# Antenna.net
KiCad netlist of a schematic drawn in Altium Designer
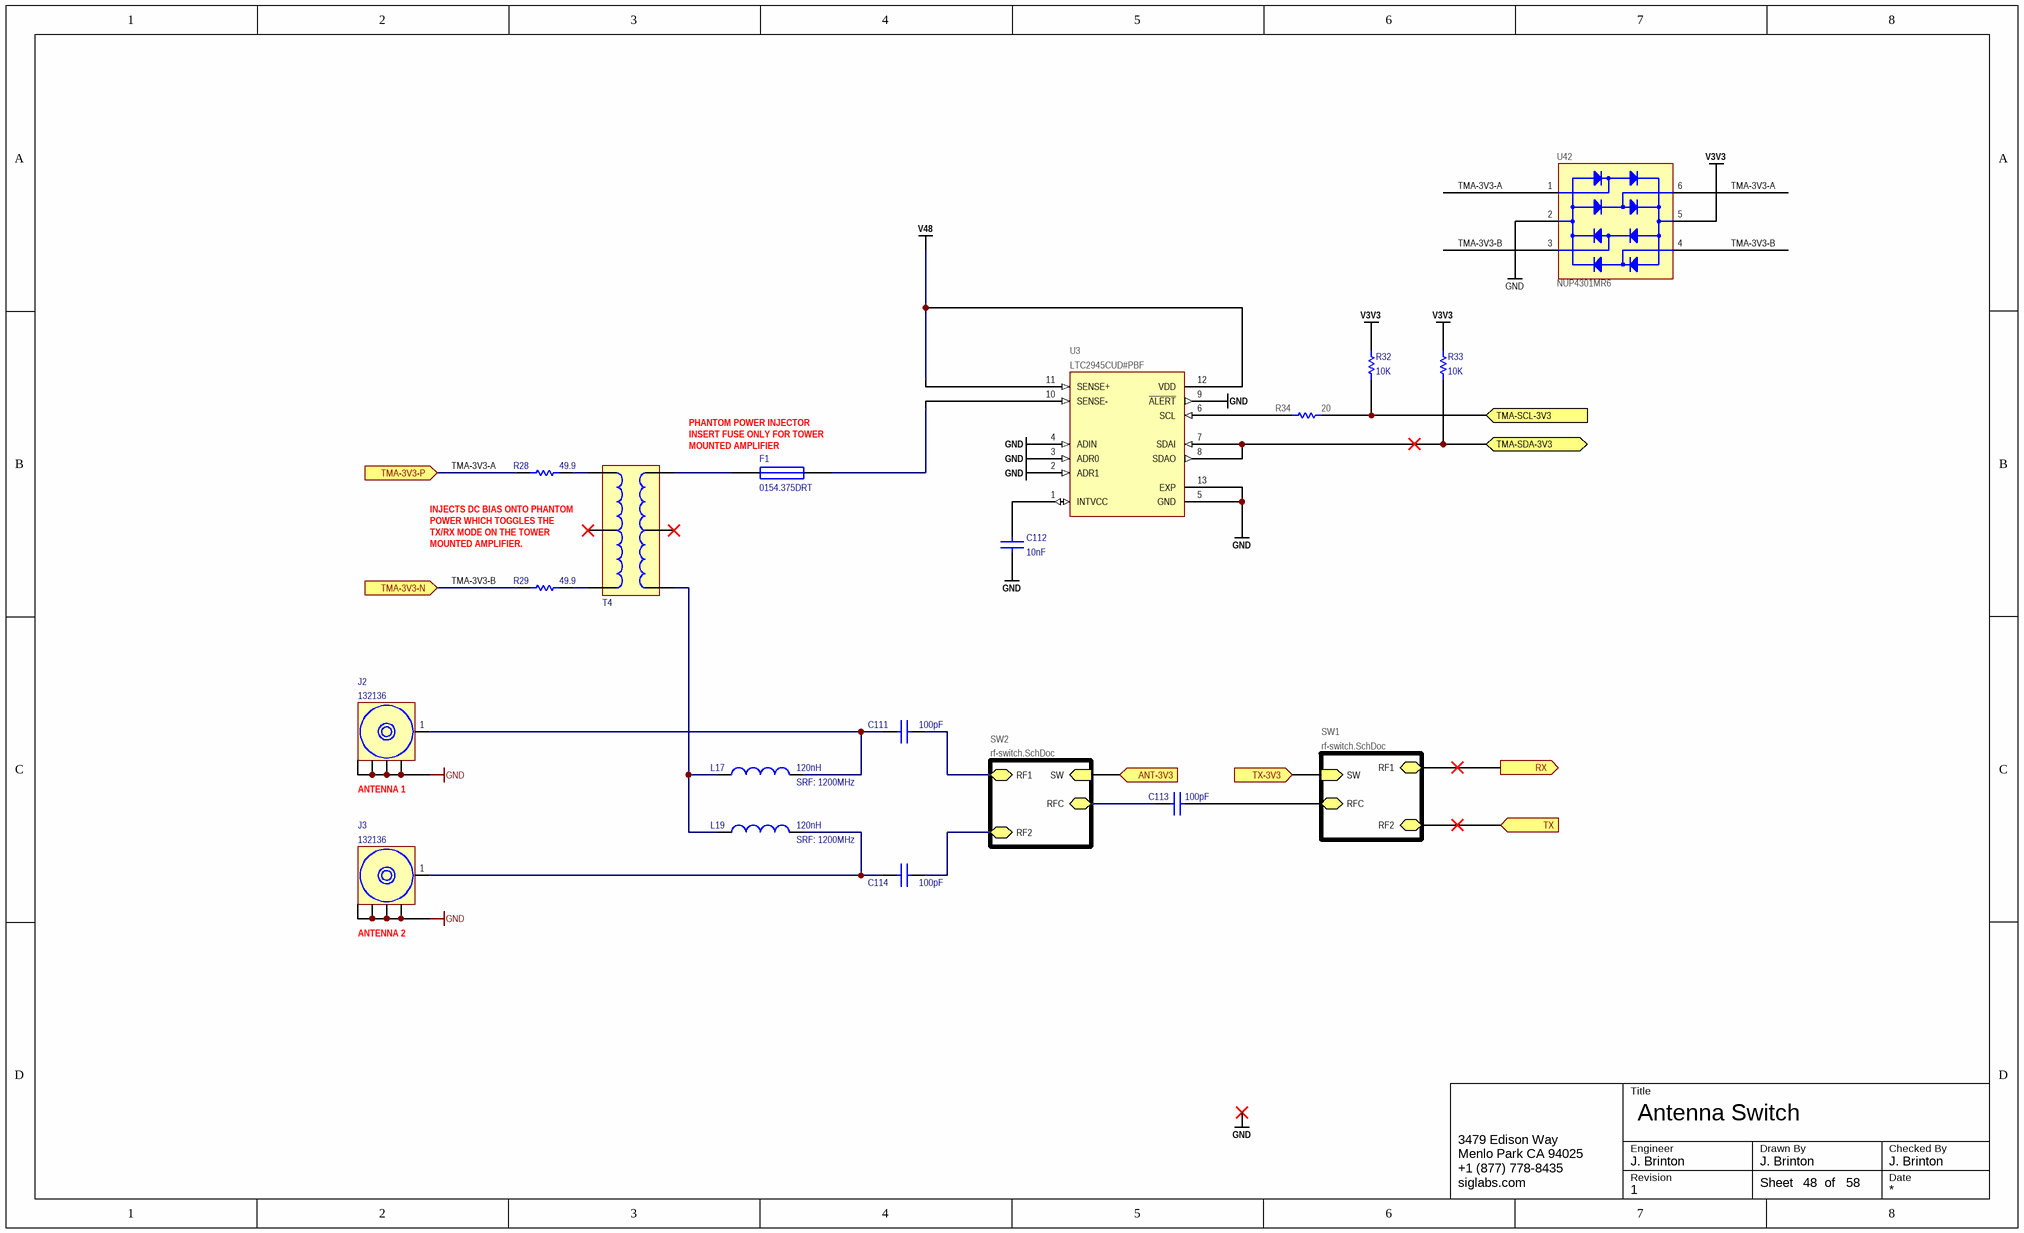
[diagram p0: Antenna.SchDoc]

(export (version "E")
  (design (tool "Eeschema 10.0.6"))
  (components
    (comp (ref "C111")
      (value "100pF")
      (footprint "CAPC100X50X55L25N")
      (description "Ceramic Capacitor 100pF ±5% 100V NP0 0402")
      (fields (field (name "VOLTAGE") "100V") (field (name "MANUFACTURER") "Kemet"))
      (libsource (lib "Graviton") (part "CAP 0603"))
    )
    (comp (ref "C112")
      (value "10nF")
      (footprint "CAPC100X50X55L25N")
      (description "Ceramic Capacitor 10nF ±10% 50V X7R 0402")
      (fields (field (name "VOLTAGE") "50V") (field (name "MANUFACTURER") "Murata"))
      (libsource (lib "Graviton") (part "CAP 0402"))
    )
    (comp (ref "C113")
      (value "100pF")
      (footprint "CAPC100X50X55L25N")
      (description "Ceramic Capacitor 100pF ±1% 25V NP0 0402")
      (fields (field (name "VOLTAGE") "25V") (field (name "MANUFACTURER") "Kemet"))
      (libsource (lib "Graviton") (part "CAP 0603"))
    )
    (comp (ref "C114")
      (value "100pF")
      (footprint "CAPC100X50X55L25N")
      (description "Ceramic Capacitor 100pF ±5% 100V NP0 0402")
      (fields (field (name "VOLTAGE") "100V") (field (name "MANUFACTURER") "Kemet"))
      (libsource (lib "Graviton") (part "CAP 0603"))
    )
    (comp (ref "F1")
      (value "0154.375DRT")
      (footprint "littelfuse:154")
      (description "154 OMNI-BLOK 0.375A Fuse and Holder")
      (fields (field (name "MANUFACTURER") "Littelfuse"))
      (libsource (lib "Miscellaneous Devices") (part "Fuse 1"))
    )
    (comp (ref "J2")
      (value "132136")
      (footprint "132136")
      (description "SMA Right Angle Connector COAX Female")
      (fields (field (name "MANUFACTURER") "Amphenol"))
      (libsource (lib "amphenol") (part "132136"))
    )
    (comp (ref "J3")
      (value "132136")
      (footprint "132136")
      (description "SMA Right Angle Connector COAX Female")
      (fields (field (name "MANUFACTURER") "Amphenol"))
      (libsource (lib "amphenol") (part "132136"))
    )
    (comp (ref "L17")
      (value "120nH")
      (footprint "0603")
      (description "Wirewound Inductor 120nH 1.1A 0603")
      (fields
        (field (name "MANUFACTURER") "Murata")
        (field (name "SRF") "1200MHz")
        (field (name "Comment") "LQW18CNR12J00D")
      )
      (libsource (lib "Graviton") (part "IND 0603"))
    )
    (comp (ref "L19")
      (value "120nH")
      (footprint "0603")
      (description "Wirewound Inductor 120nH 1.1A 0603")
      (fields
        (field (name "MANUFACTURER") "Murata")
        (field (name "SRF") "1200MHz")
        (field (name "Comment") "LQW18CNR12J00D")
      )
      (libsource (lib "Graviton") (part "IND 0603"))
    )
    (comp (ref "R28")
      (value "49.9")
      (footprint "generic:0603")
      (description "Thick Film Resistor 49.9 ±1% 0603")
      (fields (field (name "MANUFACTURER") "Panasonic") (field (name "TOLERANCE") "±1%"))
      (libsource (lib "generic") (part "RES 0603"))
    )
    (comp (ref "R29")
      (value "49.9")
      (footprint "generic:0603")
      (description "Thick Film Resistor 49.9 ±1% 0603")
      (fields (field (name "MANUFACTURER") "Panasonic") (field (name "TOLERANCE") "±1%"))
      (libsource (lib "generic") (part "RES 0603"))
    )
    (comp (ref "R32")
      (value "10K")
      (footprint "RESC1005X40N")
      (description "Thick Film 10k ±1% 0402")
      (fields (field (name "MANUFACTURER") "Panasonic") (field (name "TOLERANCE") "±1%"))
      (libsource (lib "Graviton") (part "RES 0402"))
    )
    (comp (ref "R33")
      (value "10K")
      (footprint "RESC1005X40N")
      (description "Thick Film 10k ±1% 0402")
      (fields (field (name "MANUFACTURER") "Panasonic") (field (name "TOLERANCE") "±1%"))
      (libsource (lib "Graviton") (part "RES 0402"))
    )
    (comp (ref "R34")
      (value "20")
      (footprint "RESC1005X40N")
      (description "Thick Film Resistor 20 ±1% 0.1W 75V 0402")
      (fields (field (name "TOLERANCE") "±1%") (field (name "MANUFACTURER") "Panasonic"))
      (libsource (lib "generic") (part "RES"))
    )
    (comp (ref "T4")
      (value "78253/35JC-R")
      (footprint "murata:78253/35JC-R")
      (description "Transformer")
      (fields (field (name "MANUFACTURER") "MuRata"))
      (libsource (lib "murata") (part "78253/35JC-R"))
    )
    (comp (ref "U3")
      (value "LTC2945CUD#PBF")
      (footprint "linear:QFN50P300X300X80-13N")
      (description "MS-System Monitor/Other Wide Range I2C Power Monitor %28SDAO%29")
      (fields (field (name "MF") "Linear Technology"))
      (libsource (lib "linear") (part "LTC2945CUD#PBF"))
    )
    (comp (ref "U42")
      (value "NUP4301MR6")
      (footprint "generic:SOT23-6")
      (description "4-Lane TVS Diode Array")
      (fields (field (name "MANUFACTURER") "On Semiconductor"))
      (libsource (lib "on_semi") (part "NUP4301MR6"))
    )
  )
  (nets
    (net (code "2") (name "/RF1") (class "Default")
      (node (ref "C111") (pin "1") (pinfunction "1_1") (pintype "passive"))
    )
    (net (code "3") (name "/RF2") (class "Default")
      (node (ref "C114") (pin "1") (pinfunction "1_1") (pintype "passive"))
    )
    (net (code "4") (name "/RFC") (class "Default")
      (node (ref "C113") (pin "1") (pinfunction "1_1") (pintype "passive"))
    )
    (net (code "5") (name "/RFC_1") (class "Default")
      (node (ref "C113") (pin "2") (pinfunction "2_2") (pintype "passive"))
    )
    (net (code "7") (name "/TMA-3V3-A") (class "Default")
      (node (ref "R28") (pin "1") (pinfunction "1_1") (pintype "passive"))
      (node (ref "U42") (pin "1") (pinfunction "A_1") (pintype "passive"))
      (node (ref "U42") (pin "6") (pinfunction "D_6") (pintype "passive"))
    )
    (net (code "8") (name "/TMA-3V3-B") (class "Default")
      (node (ref "R29") (pin "1") (pinfunction "1_1") (pintype "passive"))
      (node (ref "U42") (pin "3") (pinfunction "B_3") (pintype "passive"))
      (node (ref "U42") (pin "4") (pinfunction "C_4") (pintype "passive"))
    )
    (net (code "9") (name "/TMA-SCL-3V3") (class "Default")
      (node (ref "R32") (pin "1") (pinfunction "1_1") (pintype "passive"))
      (node (ref "R34") (pin "2") (pinfunction "2_2") (pintype "passive"))
    )
    (net (code "10") (name "/TMA-SDA-3V3") (class "Default")
      (node (ref "R33") (pin "1") (pinfunction "1_1") (pintype "passive"))
      (node (ref "U3") (pin "7") (pinfunction "SDAI_7") (pintype "input"))
      (node (ref "U3") (pin "8") (pinfunction "SDAO_8") (pintype "output"))
    )
    (net (code "13") (name "GND") (class "Default")
      (node (ref "C112") (pin "1") (pinfunction "1_1") (pintype "passive"))
      (node (ref "J2") (pin "2") (pinfunction "GND_2") (pintype "passive"))
      (node (ref "J2") (pin "3") (pinfunction "GND_3") (pintype "passive"))
      (node (ref "J2") (pin "4") (pinfunction "GND_4") (pintype "passive"))
      (node (ref "J2") (pin "5") (pinfunction "GND_5") (pintype "passive"))
      (node (ref "J3") (pin "2") (pinfunction "GND_2") (pintype "passive"))
      (node (ref "J3") (pin "3") (pinfunction "GND_3") (pintype "passive"))
      (node (ref "J3") (pin "4") (pinfunction "GND_4") (pintype "passive"))
      (node (ref "J3") (pin "5") (pinfunction "GND_5") (pintype "passive"))
      (node (ref "U3") (pin "13") (pinfunction "EXP_13") (pintype "power_in"))
      (node (ref "U3") (pin "2") (pinfunction "ADR1_2") (pintype "input"))
      (node (ref "U3") (pin "3") (pinfunction "ADR0_3") (pintype "input"))
      (node (ref "U3") (pin "4") (pinfunction "ADIN_4") (pintype "input"))
      (node (ref "U3") (pin "5") (pinfunction "GND_5") (pintype "power_in"))
      (node (ref "U3") (pin "9") (pinfunction "~{ALERT}_9") (pintype "output"))
      (node (ref "U42") (pin "2") (pinfunction "VN_2") (pintype "passive"))
    )
    (net (code "14") (name "Net-(F1-Pad1)") (class "Default")
      (node (ref "F1") (pin "1") (pinfunction "1_1") (pintype "passive"))
      (node (ref "T4") (pin "6") (pinfunction "6_6") (pintype "passive"))
    )
    (net (code "15") (name "Net-(J2-CENTER)") (class "Default")
      (node (ref "C111") (pin "2") (pinfunction "2_2") (pintype "passive"))
      (node (ref "J2") (pin "1") (pinfunction "CENTER_1") (pintype "passive"))
      (node (ref "L17") (pin "2") (pinfunction "2_2") (pintype "passive"))
    )
    (net (code "16") (name "Net-(J3-CENTER)") (class "Default")
      (node (ref "C114") (pin "2") (pinfunction "2_2") (pintype "passive"))
      (node (ref "J3") (pin "1") (pinfunction "CENTER_1") (pintype "passive"))
      (node (ref "L19") (pin "2") (pinfunction "2_2") (pintype "passive"))
    )
    (net (code "17") (name "Net-(L17-Pad1)") (class "Default")
      (node (ref "L17") (pin "1") (pinfunction "1_1") (pintype "passive"))
      (node (ref "L19") (pin "1") (pinfunction "1_1") (pintype "passive"))
      (node (ref "T4") (pin "4") (pinfunction "4_4") (pintype "passive"))
    )
    (net (code "18") (name "Net-(R28-Pad2)") (class "Default")
      (node (ref "R28") (pin "2") (pinfunction "2_2") (pintype "passive"))
      (node (ref "T4") (pin "1") (pinfunction "1_1") (pintype "passive"))
    )
    (net (code "19") (name "Net-(R29-Pad2)") (class "Default")
      (node (ref "R29") (pin "2") (pinfunction "2_2") (pintype "passive"))
      (node (ref "T4") (pin "3") (pinfunction "3_3") (pintype "passive"))
    )
    (net (code "20") (name "Net-(U3-INTVCC)") (class "Default")
      (node (ref "C112") (pin "2") (pinfunction "2_2") (pintype "passive"))
      (node (ref "U3") (pin "1") (pinfunction "INTVCC_1") (pintype "bidirectional"))
    )
    (net (code "21") (name "Net-(U3-SCL)") (class "Default")
      (node (ref "R34") (pin "1") (pinfunction "1_1") (pintype "passive"))
      (node (ref "U3") (pin "6") (pinfunction "SCL_6") (pintype "input"))
    )
    (net (code "22") (name "Net-(U3-SENSE-)") (class "Default")
      (node (ref "F1") (pin "2") (pinfunction "2_2") (pintype "passive"))
      (node (ref "U3") (pin "10") (pinfunction "SENSE-_10") (pintype "input"))
    )
    (net (code "23") (name "V3V3") (class "Default")
      (node (ref "R32") (pin "2") (pinfunction "2_2") (pintype "passive"))
      (node (ref "R33") (pin "2") (pinfunction "2_2") (pintype "passive"))
      (node (ref "U42") (pin "5") (pinfunction "VP_5") (pintype "passive"))
    )
    (net (code "24") (name "V48") (class "Default")
      (node (ref "U3") (pin "11") (pinfunction "SENSE+_11") (pintype "input"))
      (node (ref "U3") (pin "12") (pinfunction "VDD_12") (pintype "power_in"))
    )
    (net (code "25") (name "unconnected-(T4-Pad2)") (class "Default")
      (node (ref "T4") (pin "2") (pinfunction "2_2") (pintype "passive+no_connect"))
    )
    (net (code "26") (name "unconnected-(T4-Pad5)") (class "Default")
      (node (ref "T4") (pin "5") (pinfunction "5_5") (pintype "passive+no_connect"))
    )
  )
)
